# IR4427.net
KiCad netlist of a schematic drawn in EAGLE
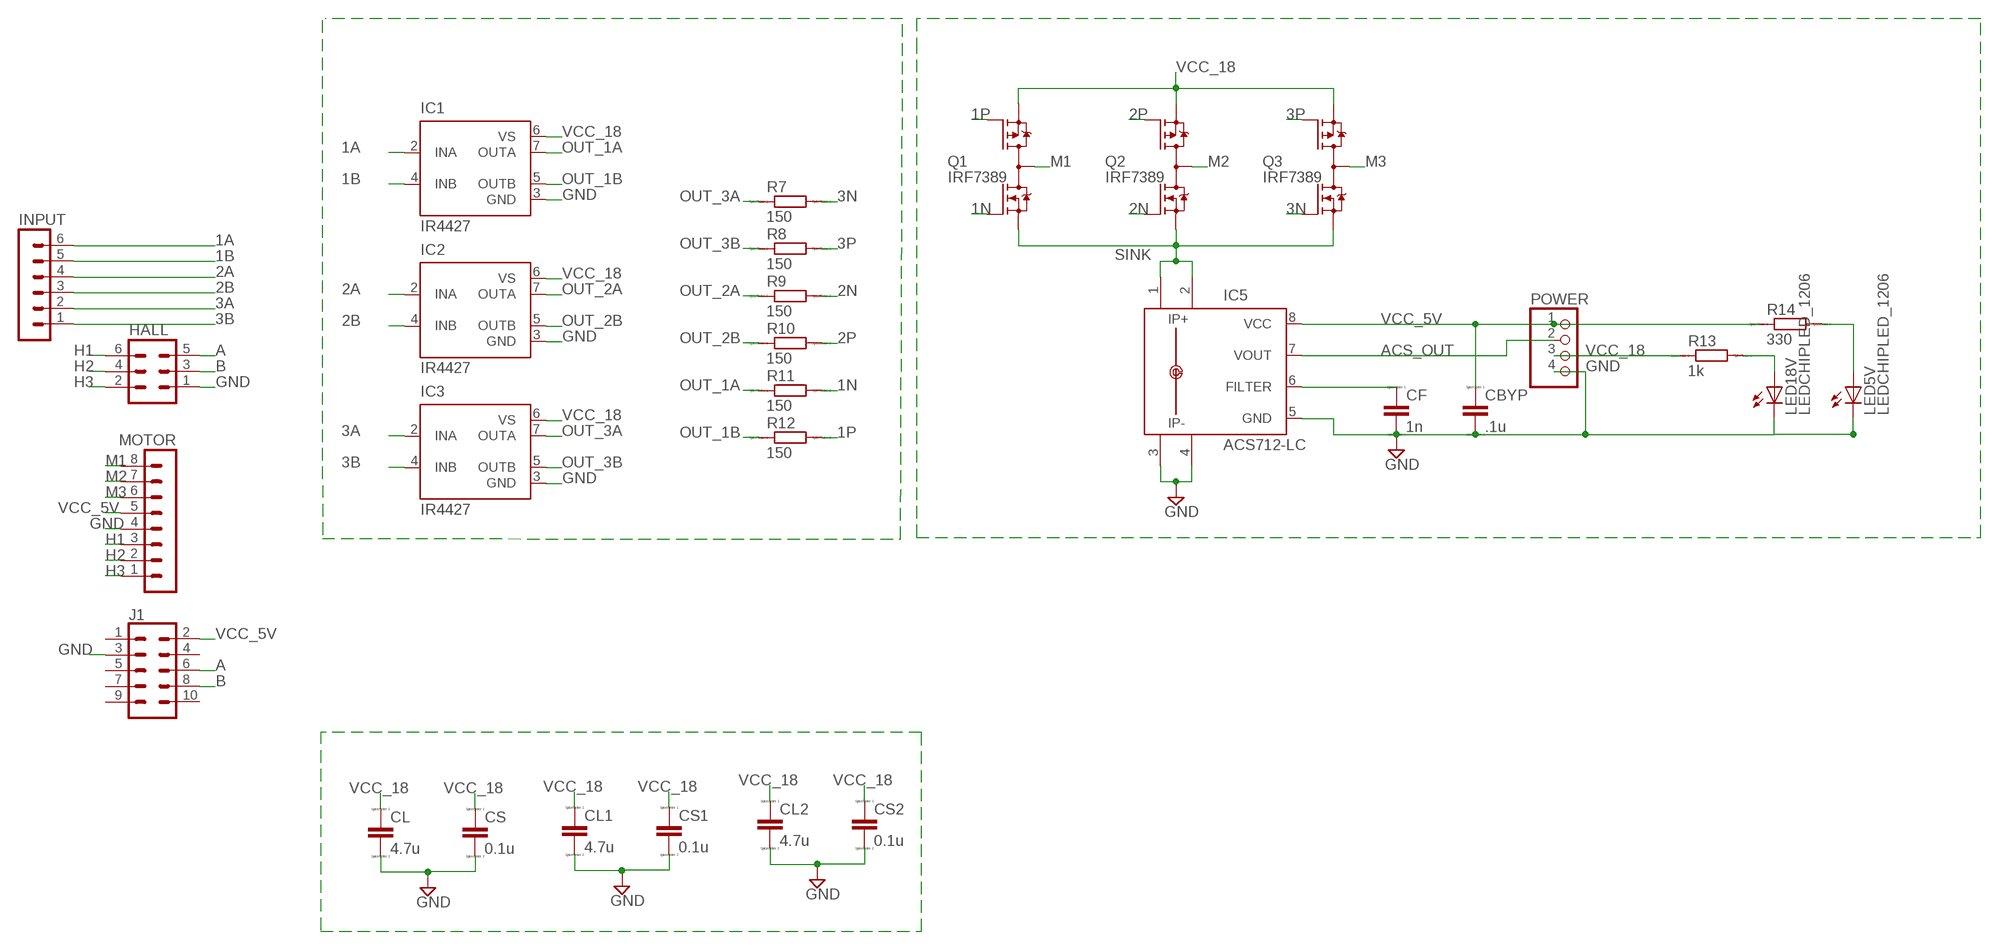
[diagram p0: schematic, sheet 1]

(export (version "E")
  (design (tool "Eeschema 10.0.6"))
  (components
    (comp (ref "CBYP")
      (value ".1u")
      (footprint "eagle-import:C1206")
      (libsource (lib "eagle-import") (part "CC1206"))
    )
    (comp (ref "CF")
      (value "1n")
      (footprint "eagle-import:C1206")
      (libsource (lib "eagle-import") (part "CC1206"))
    )
    (comp (ref "CL")
      (value "4.7u")
      (footprint "eagle-import:C1206")
      (libsource (lib "eagle-import") (part "CC1206"))
    )
    (comp (ref "CL1")
      (value "4.7u")
      (footprint "eagle-import:C1206")
      (libsource (lib "eagle-import") (part "CC1206"))
    )
    (comp (ref "CL2")
      (value "4.7u")
      (footprint "eagle-import:C1206")
      (libsource (lib "eagle-import") (part "CC1206"))
    )
    (comp (ref "CS")
      (value "0.1u")
      (footprint "eagle-import:C1206")
      (libsource (lib "eagle-import") (part "CC1206"))
    )
    (comp (ref "CS1")
      (value "0.1u")
      (footprint "eagle-import:C1206")
      (libsource (lib "eagle-import") (part "CC1206"))
    )
    (comp (ref "CS2")
      (value "0.1u")
      (footprint "eagle-import:C1206")
      (libsource (lib "eagle-import") (part "CC1206"))
    )
    (comp (ref "HALL")
      (value "MA03-2")
      (footprint "eagle-import:MA03-2")
      (libsource (lib "eagle-import") (part "MA03-2"))
    )
    (comp (ref "IC1")
      (value "IR4427")
      (footprint "eagle-import:DIL08")
      (fields (field (name "MF") "INTERNATIONAL RECTIFIER(IR)"))
      (libsource (lib "eagle-import") (part "IR4427"))
    )
    (comp (ref "IC2")
      (value "IR4427")
      (footprint "eagle-import:DIL08")
      (fields (field (name "MF") "INTERNATIONAL RECTIFIER(IR)"))
      (libsource (lib "eagle-import") (part "IR4427"))
    )
    (comp (ref "IC3")
      (value "IR4427")
      (footprint "eagle-import:DIL08")
      (fields (field (name "MF") "INTERNATIONAL RECTIFIER(IR)"))
      (libsource (lib "eagle-import") (part "IR4427"))
    )
    (comp (ref "IC5")
      (value "ACS712-LC")
      (footprint "eagle-import:SOIC8")
      (libsource (lib "eagle-import") (part "ACS712-LC"))
    )
    (comp (ref "INPUT")
      (value "MA06-1")
      (footprint "eagle-import:MA06-1")
      (libsource (lib "eagle-import") (part "MA06-1"))
    )
    (comp (ref "J1")
      (value "CONN_05X2SHD_LOCK")
      (footprint "eagle-import:2X5-SHROUDED_LOCK")
      (libsource (lib "eagle-import") (part "CONN_05X2SHD_LOCK"))
    )
    (comp (ref "LED5V")
      (value "LEDCHIPLED_1206")
      (footprint "eagle-import:CHIPLED_1206")
      (libsource (lib "eagle-import") (part "LEDCHIPLED_1206"))
    )
    (comp (ref "LED18V")
      (value "LEDCHIPLED_1206")
      (footprint "eagle-import:CHIPLED_1206")
      (libsource (lib "eagle-import") (part "LEDCHIPLED_1206"))
    )
    (comp (ref "MOTOR")
      (value "MA08-1")
      (footprint "eagle-import:MA08-1")
      (libsource (lib "eagle-import") (part "MA08-1"))
    )
    (comp (ref "POWER")
      (value "PINHD-1X4")
      (footprint "eagle-import:1X04")
      (libsource (lib "eagle-import") (part "PINHD-1X4"))
    )
    (comp (ref "Q1")
      (value "IRF7389")
      (footprint "eagle-import:SO08-IRF")
      (libsource (lib "eagle-import") (part "IRF7389"))
    )
    (comp (ref "Q2")
      (value "IRF7389")
      (footprint "eagle-import:SO08-IRF")
      (libsource (lib "eagle-import") (part "IRF7389"))
    )
    (comp (ref "Q3")
      (value "IRF7389")
      (footprint "eagle-import:SO08-IRF")
      (libsource (lib "eagle-import") (part "IRF7389"))
    )
    (comp (ref "R7")
      (value "150")
      (footprint "eagle-import:R1206")
      (libsource (lib "eagle-import") (part "RR1206"))
    )
    (comp (ref "R8")
      (value "150")
      (footprint "eagle-import:R1206")
      (libsource (lib "eagle-import") (part "RR1206"))
    )
    (comp (ref "R9")
      (value "150")
      (footprint "eagle-import:R1206")
      (libsource (lib "eagle-import") (part "RR1206"))
    )
    (comp (ref "R10")
      (value "150")
      (footprint "eagle-import:R1206")
      (libsource (lib "eagle-import") (part "RR1206"))
    )
    (comp (ref "R11")
      (value "150")
      (footprint "eagle-import:R1206")
      (libsource (lib "eagle-import") (part "RR1206"))
    )
    (comp (ref "R12")
      (value "150")
      (footprint "eagle-import:R1206")
      (libsource (lib "eagle-import") (part "RR1206"))
    )
    (comp (ref "R13")
      (value "1k")
      (footprint "eagle-import:R1206")
      (libsource (lib "eagle-import") (part "RR1206"))
    )
    (comp (ref "R14")
      (value "330")
      (footprint "eagle-import:R1206")
      (libsource (lib "eagle-import") (part "RR1206"))
    )
  )
  (nets
    (net (code "1") (name "/1A") (class "Default")
      (node (ref "IC1") (pin "2") (pinfunction "INA_2") (pintype "input"))
      (node (ref "INPUT") (pin "6") (pinfunction "6_6") (pintype "passive"))
    )
    (net (code "2") (name "/1B") (class "Default")
      (node (ref "IC1") (pin "4") (pinfunction "INB_4") (pintype "input"))
      (node (ref "INPUT") (pin "5") (pinfunction "5_5") (pintype "passive"))
    )
    (net (code "3") (name "/1N") (class "Default")
      (node (ref "Q1") (pin "2") (pinfunction "N-G_2") (pintype "passive"))
      (node (ref "R11") (pin "2") (pinfunction "2_2") (pintype "passive"))
    )
    (net (code "4") (name "/1P") (class "Default")
      (node (ref "Q1") (pin "4") (pinfunction "P-G_4") (pintype "passive"))
      (node (ref "R12") (pin "2") (pinfunction "2_2") (pintype "passive"))
    )
    (net (code "5") (name "/2A") (class "Default")
      (node (ref "IC2") (pin "2") (pinfunction "INA_2") (pintype "input"))
      (node (ref "INPUT") (pin "4") (pinfunction "4_4") (pintype "passive"))
    )
    (net (code "6") (name "/2B") (class "Default")
      (node (ref "IC2") (pin "4") (pinfunction "INB_4") (pintype "input"))
      (node (ref "INPUT") (pin "3") (pinfunction "3_3") (pintype "passive"))
    )
    (net (code "7") (name "/2N") (class "Default")
      (node (ref "Q2") (pin "2") (pinfunction "N-G_2") (pintype "passive"))
      (node (ref "R9") (pin "2") (pinfunction "2_2") (pintype "passive"))
    )
    (net (code "8") (name "/2P") (class "Default")
      (node (ref "Q2") (pin "4") (pinfunction "P-G_4") (pintype "passive"))
      (node (ref "R10") (pin "2") (pinfunction "2_2") (pintype "passive"))
    )
    (net (code "9") (name "/3A") (class "Default")
      (node (ref "IC3") (pin "2") (pinfunction "INA_2") (pintype "input"))
      (node (ref "INPUT") (pin "2") (pinfunction "2_2") (pintype "passive"))
    )
    (net (code "10") (name "/3B") (class "Default")
      (node (ref "IC3") (pin "4") (pinfunction "INB_4") (pintype "input"))
      (node (ref "INPUT") (pin "1") (pinfunction "1_1") (pintype "passive"))
    )
    (net (code "11") (name "/3N") (class "Default")
      (node (ref "Q3") (pin "2") (pinfunction "N-G_2") (pintype "passive"))
      (node (ref "R7") (pin "2") (pinfunction "2_2") (pintype "passive"))
    )
    (net (code "12") (name "/3P") (class "Default")
      (node (ref "Q3") (pin "4") (pinfunction "P-G_4") (pintype "passive"))
      (node (ref "R8") (pin "2") (pinfunction "2_2") (pintype "passive"))
    )
    (net (code "13") (name "/A") (class "Default")
      (node (ref "HALL") (pin "5") (pinfunction "5_5") (pintype "passive"))
      (node (ref "J1") (pin "6") (pinfunction "6_6") (pintype "passive"))
    )
    (net (code "14") (name "/ACS_OUT") (class "Default")
      (node (ref "IC5") (pin "7") (pinfunction "VOUT_7") (pintype "output"))
      (node (ref "POWER") (pin "2") (pinfunction "2_2") (pintype "passive"))
    )
    (net (code "15") (name "/B") (class "Default")
      (node (ref "HALL") (pin "3") (pinfunction "3_3") (pintype "passive"))
      (node (ref "J1") (pin "8") (pinfunction "8_8") (pintype "passive"))
    )
    (net (code "16") (name "/H1") (class "Default")
      (node (ref "HALL") (pin "6") (pinfunction "6_6") (pintype "passive"))
      (node (ref "MOTOR") (pin "3") (pinfunction "3_3") (pintype "passive"))
    )
    (net (code "17") (name "/H2") (class "Default")
      (node (ref "HALL") (pin "4") (pinfunction "4_4") (pintype "passive"))
      (node (ref "MOTOR") (pin "2") (pinfunction "2_2") (pintype "passive"))
    )
    (net (code "18") (name "/H3") (class "Default")
      (node (ref "HALL") (pin "2") (pinfunction "2_2") (pintype "passive"))
      (node (ref "MOTOR") (pin "1") (pinfunction "1_1") (pintype "passive"))
    )
    (net (code "19") (name "/M1") (class "Default")
      (node (ref "MOTOR") (pin "8") (pinfunction "8_8") (pintype "passive"))
      (node (ref "Q1") (pin "5") (pinfunction "D_5") (pintype "passive"))
      (node (ref "Q1") (pin "6") (pinfunction "D_6") (pintype "passive"))
      (node (ref "Q1") (pin "7") (pinfunction "D_7") (pintype "passive"))
      (node (ref "Q1") (pin "8") (pinfunction "D_8") (pintype "passive"))
    )
    (net (code "20") (name "/M2") (class "Default")
      (node (ref "MOTOR") (pin "7") (pinfunction "7_7") (pintype "passive"))
      (node (ref "Q2") (pin "5") (pinfunction "D_5") (pintype "passive"))
      (node (ref "Q2") (pin "6") (pinfunction "D_6") (pintype "passive"))
      (node (ref "Q2") (pin "7") (pinfunction "D_7") (pintype "passive"))
      (node (ref "Q2") (pin "8") (pinfunction "D_8") (pintype "passive"))
    )
    (net (code "21") (name "/M3") (class "Default")
      (node (ref "MOTOR") (pin "6") (pinfunction "6_6") (pintype "passive"))
      (node (ref "Q3") (pin "5") (pinfunction "D_5") (pintype "passive"))
      (node (ref "Q3") (pin "6") (pinfunction "D_6") (pintype "passive"))
      (node (ref "Q3") (pin "7") (pinfunction "D_7") (pintype "passive"))
      (node (ref "Q3") (pin "8") (pinfunction "D_8") (pintype "passive"))
    )
    (net (code "22") (name "/OUT_1A") (class "Default")
      (node (ref "IC1") (pin "7") (pinfunction "OUTA_7") (pintype "output"))
      (node (ref "R11") (pin "1") (pinfunction "1_1") (pintype "passive"))
    )
    (net (code "23") (name "/OUT_1B") (class "Default")
      (node (ref "IC1") (pin "5") (pinfunction "OUTB_5") (pintype "output"))
      (node (ref "R12") (pin "1") (pinfunction "1_1") (pintype "passive"))
    )
    (net (code "24") (name "/OUT_2A") (class "Default")
      (node (ref "IC2") (pin "7") (pinfunction "OUTA_7") (pintype "output"))
      (node (ref "R9") (pin "1") (pinfunction "1_1") (pintype "passive"))
    )
    (net (code "25") (name "/OUT_2B") (class "Default")
      (node (ref "IC2") (pin "5") (pinfunction "OUTB_5") (pintype "output"))
      (node (ref "R10") (pin "1") (pinfunction "1_1") (pintype "passive"))
    )
    (net (code "26") (name "/OUT_3A") (class "Default")
      (node (ref "IC3") (pin "7") (pinfunction "OUTA_7") (pintype "output"))
      (node (ref "R7") (pin "1") (pinfunction "1_1") (pintype "passive"))
    )
    (net (code "27") (name "/OUT_3B") (class "Default")
      (node (ref "IC3") (pin "5") (pinfunction "OUTB_5") (pintype "output"))
      (node (ref "R8") (pin "1") (pinfunction "1_1") (pintype "passive"))
    )
    (net (code "28") (name "/SINK") (class "Default")
      (node (ref "IC5") (pin "1") (pinfunction "IP+_1") (pintype "passive"))
      (node (ref "IC5") (pin "2") (pinfunction "IP+1_2") (pintype "passive"))
      (node (ref "Q1") (pin "1") (pinfunction "N-S_1") (pintype "passive"))
      (node (ref "Q2") (pin "1") (pinfunction "N-S_1") (pintype "passive"))
      (node (ref "Q3") (pin "1") (pinfunction "N-S_1") (pintype "passive"))
    )
    (net (code "29") (name "/VCC_5V") (class "Default")
      (node (ref "CBYP") (pin "1") (pinfunction "1_1") (pintype "passive"))
      (node (ref "IC5") (pin "8") (pinfunction "VCC_8") (pintype "power_in"))
      (node (ref "J1") (pin "2") (pinfunction "2_2") (pintype "passive"))
      (node (ref "MOTOR") (pin "5") (pinfunction "5_5") (pintype "passive"))
      (node (ref "POWER") (pin "1") (pinfunction "1_1") (pintype "passive"))
      (node (ref "R14") (pin "1") (pinfunction "1_1") (pintype "passive"))
    )
    (net (code "30") (name "/VCC_18") (class "Default")
      (node (ref "CL") (pin "1") (pinfunction "1_1") (pintype "passive"))
      (node (ref "CL1") (pin "1") (pinfunction "1_1") (pintype "passive"))
      (node (ref "CL2") (pin "1") (pinfunction "1_1") (pintype "passive"))
      (node (ref "CS") (pin "1") (pinfunction "1_1") (pintype "passive"))
      (node (ref "CS1") (pin "1") (pinfunction "1_1") (pintype "passive"))
      (node (ref "CS2") (pin "1") (pinfunction "1_1") (pintype "passive"))
      (node (ref "IC1") (pin "6") (pinfunction "VS_6") (pintype "power_in"))
      (node (ref "IC2") (pin "6") (pinfunction "VS_6") (pintype "power_in"))
      (node (ref "IC3") (pin "6") (pinfunction "VS_6") (pintype "power_in"))
      (node (ref "POWER") (pin "3") (pinfunction "3_3") (pintype "passive"))
      (node (ref "Q1") (pin "3") (pinfunction "P-S_3") (pintype "passive"))
      (node (ref "Q2") (pin "3") (pinfunction "P-S_3") (pintype "passive"))
      (node (ref "Q3") (pin "3") (pinfunction "P-S_3") (pintype "passive"))
      (node (ref "R13") (pin "1") (pinfunction "1_1") (pintype "passive"))
    )
    (net (code "31") (name "GND") (class "Default")
      (node (ref "CBYP") (pin "2") (pinfunction "2_2") (pintype "passive"))
      (node (ref "CF") (pin "2") (pinfunction "2_2") (pintype "passive"))
      (node (ref "CL") (pin "2") (pinfunction "2_2") (pintype "passive"))
      (node (ref "CL1") (pin "2") (pinfunction "2_2") (pintype "passive"))
      (node (ref "CL2") (pin "2") (pinfunction "2_2") (pintype "passive"))
      (node (ref "CS") (pin "2") (pinfunction "2_2") (pintype "passive"))
      (node (ref "CS1") (pin "2") (pinfunction "2_2") (pintype "passive"))
      (node (ref "CS2") (pin "2") (pinfunction "2_2") (pintype "passive"))
      (node (ref "HALL") (pin "1") (pinfunction "1_1") (pintype "passive"))
      (node (ref "IC1") (pin "3") (pinfunction "GND_3") (pintype "power_in"))
      (node (ref "IC2") (pin "3") (pinfunction "GND_3") (pintype "power_in"))
      (node (ref "IC3") (pin "3") (pinfunction "GND_3") (pintype "power_in"))
      (node (ref "IC5") (pin "3") (pinfunction "IP-_3") (pintype "passive"))
      (node (ref "IC5") (pin "4") (pinfunction "IP-1_4") (pintype "passive"))
      (node (ref "IC5") (pin "5") (pinfunction "GND_5") (pintype "power_in"))
      (node (ref "J1") (pin "3") (pinfunction "3_3") (pintype "passive"))
      (node (ref "LED18V") (pin "C") (pinfunction "C_C") (pintype "passive"))
      (node (ref "LED5V") (pin "C") (pinfunction "C_C") (pintype "passive"))
      (node (ref "MOTOR") (pin "4") (pinfunction "4_4") (pintype "passive"))
      (node (ref "POWER") (pin "4") (pinfunction "4_4") (pintype "passive"))
    )
    (net (code "32") (name "Net-(IC5-FILTER)") (class "Default")
      (node (ref "CF") (pin "1") (pinfunction "1_1") (pintype "passive"))
      (node (ref "IC5") (pin "6") (pinfunction "FILTER_6") (pintype "bidirectional"))
    )
    (net (code "33") (name "Net-(LED5V-PadA)") (class "Default")
      (node (ref "LED5V") (pin "A") (pinfunction "A_A") (pintype "passive"))
      (node (ref "R14") (pin "2") (pinfunction "2_2") (pintype "passive"))
    )
    (net (code "34") (name "Net-(LED18V-PadA)") (class "Default")
      (node (ref "LED18V") (pin "A") (pinfunction "A_A") (pintype "passive"))
      (node (ref "R13") (pin "2") (pinfunction "2_2") (pintype "passive"))
    )
    (net (code "35") (name "unconnected-(J1-Pad1)") (class "Default")
      (node (ref "J1") (pin "1") (pinfunction "1_1") (pintype "passive"))
    )
    (net (code "36") (name "unconnected-(J1-Pad4)") (class "Default")
      (node (ref "J1") (pin "4") (pinfunction "4_4") (pintype "passive"))
    )
    (net (code "37") (name "unconnected-(J1-Pad5)") (class "Default")
      (node (ref "J1") (pin "5") (pinfunction "5_5") (pintype "passive"))
    )
    (net (code "38") (name "unconnected-(J1-Pad7)") (class "Default")
      (node (ref "J1") (pin "7") (pinfunction "7_7") (pintype "passive"))
    )
    (net (code "39") (name "unconnected-(J1-Pad9)") (class "Default")
      (node (ref "J1") (pin "9") (pinfunction "9_9") (pintype "passive"))
    )
    (net (code "40") (name "unconnected-(J1-Pad10)") (class "Default")
      (node (ref "J1") (pin "10") (pinfunction "10_10") (pintype "passive"))
    )
  )
)
